# Osmofl2k_adapter_threechannel.net
KiCad netlist of a schematic drawn in EAGLE
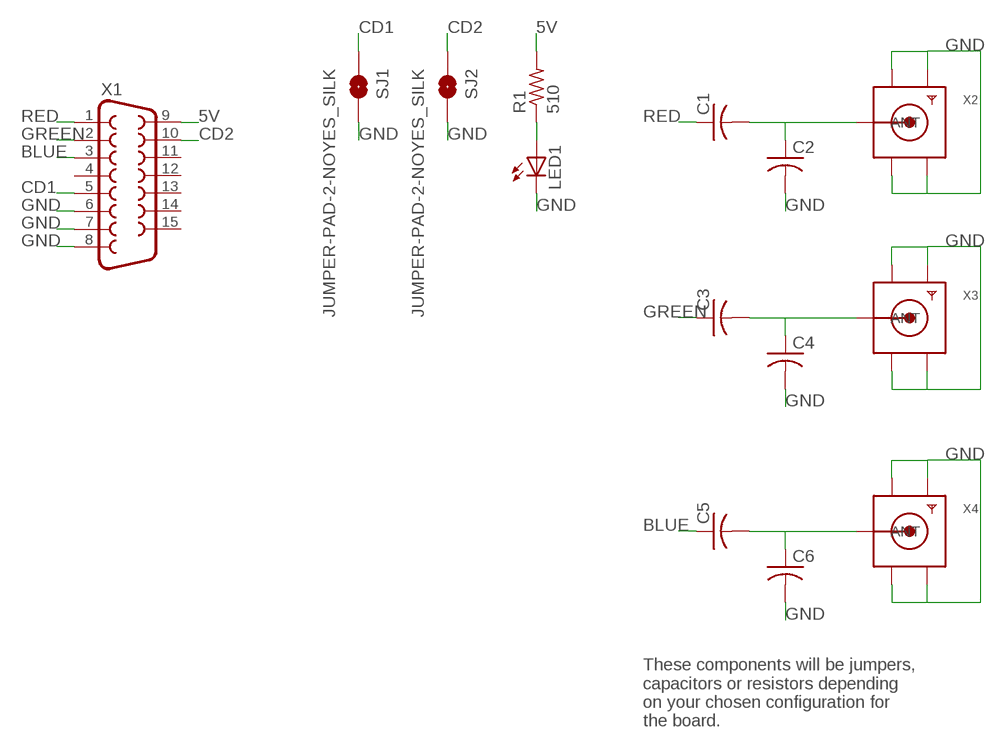
[diagram p0: schematic, sheet 1]

(export (version "E")
  (design (tool "Eeschema 10.0.6"))
  (components
    (comp (ref "C1")
      (value "C-USC0603")
      (footprint "eagle-import:C0603")
      (libsource (lib "eagle-import") (part "C-USC0603"))
    )
    (comp (ref "C2")
      (value "C-USC0603")
      (footprint "eagle-import:C0603")
      (libsource (lib "eagle-import") (part "C-USC0603"))
    )
    (comp (ref "C3")
      (value "C-USC0603")
      (footprint "eagle-import:C0603")
      (libsource (lib "eagle-import") (part "C-USC0603"))
    )
    (comp (ref "C4")
      (value "C-USC0603")
      (footprint "eagle-import:C0603")
      (libsource (lib "eagle-import") (part "C-USC0603"))
    )
    (comp (ref "C5")
      (value "C-USC0603")
      (footprint "eagle-import:C0603")
      (libsource (lib "eagle-import") (part "C-USC0603"))
    )
    (comp (ref "C6")
      (value "C-USC0603")
      (footprint "eagle-import:C0603")
      (libsource (lib "eagle-import") (part "C-USC0603"))
    )
    (comp (ref "LED1")
      (value "LEDCHIPLED_0805")
      (footprint "eagle-import:CHIPLED_0805")
      (libsource (lib "eagle-import") (part "LEDCHIPLED_0805"))
    )
    (comp (ref "R1")
      (value "510")
      (footprint "eagle-import:R0805")
      (libsource (lib "eagle-import") (part "R-US_R0805"))
    )
    (comp (ref "SJ1")
      (value "JUMPER-PAD-2-NOYES_SILK")
      (footprint "eagle-import:PAD-JUMPER-2-NO_YES_SILK")
      (libsource (lib "eagle-import") (part "JUMPER-PAD-2-NOYES_SILK"))
    )
    (comp (ref "SJ2")
      (value "JUMPER-PAD-2-NOYES_SILK")
      (footprint "eagle-import:PAD-JUMPER-2-NO_YES_SILK")
      (libsource (lib "eagle-import") (part "JUMPER-PAD-2-NOYES_SILK"))
    )
    (comp (ref "X1")
      (value "F15HDH")
      (footprint "eagle-import:HDF15H")
      (libsource (lib "eagle-import") (part "F15HDH"))
    )
    (comp (ref "X2")
      (value "SMACONNECTOR_EDGE")
      (footprint "eagle-import:SMA_EDGELAUNCH")
      (libsource (lib "eagle-import") (part "SMACONNECTOR_EDGE"))
    )
    (comp (ref "X3")
      (value "SMACONNECTOR_EDGE")
      (footprint "eagle-import:SMA_EDGELAUNCH")
      (libsource (lib "eagle-import") (part "SMACONNECTOR_EDGE"))
    )
    (comp (ref "X4")
      (value "SMACONNECTOR_EDGE")
      (footprint "eagle-import:SMA_EDGELAUNCH")
      (libsource (lib "eagle-import") (part "SMACONNECTOR_EDGE"))
    )
  )
  (nets
    (net (code "1") (name "/5V") (class "Default")
      (node (ref "R1") (pin "2") (pinfunction "2_2") (pintype "passive"))
      (node (ref "X1") (pin "9") (pinfunction "9_9") (pintype "passive"))
    )
    (net (code "2") (name "/BLUE") (class "Default")
      (node (ref "C5") (pin "1") (pinfunction "1_1") (pintype "passive"))
      (node (ref "X1") (pin "3") (pinfunction "3_3") (pintype "passive"))
    )
    (net (code "3") (name "/CD1") (class "Default")
      (node (ref "SJ1") (pin "1") (pinfunction "1_1") (pintype "passive"))
      (node (ref "X1") (pin "5") (pinfunction "5_5") (pintype "passive"))
    )
    (net (code "4") (name "/CD2") (class "Default")
      (node (ref "SJ2") (pin "1") (pinfunction "1_1") (pintype "passive"))
      (node (ref "X1") (pin "10") (pinfunction "10_10") (pintype "passive"))
    )
    (net (code "5") (name "/GND") (class "Default")
      (node (ref "C2") (pin "2") (pinfunction "2_2") (pintype "passive"))
      (node (ref "C4") (pin "2") (pinfunction "2_2") (pintype "passive"))
      (node (ref "C6") (pin "2") (pinfunction "2_2") (pintype "passive"))
      (node (ref "LED1") (pin "C") (pinfunction "C_C") (pintype "passive"))
      (node (ref "SJ1") (pin "2") (pinfunction "2_2") (pintype "passive"))
      (node (ref "SJ2") (pin "2") (pinfunction "2_2") (pintype "passive"))
      (node (ref "X1") (pin "6") (pinfunction "6_6") (pintype "passive"))
      (node (ref "X1") (pin "7") (pinfunction "7_7") (pintype "passive"))
      (node (ref "X1") (pin "8") (pinfunction "8_8") (pintype "passive"))
      (node (ref "X2") (pin "GND@1") (pinfunction "GND4_GND@1") (pintype "power_in"))
      (node (ref "X2") (pin "GND@2") (pinfunction "GND3_GND@2") (pintype "power_in"))
      (node (ref "X2") (pin "GND@3") (pinfunction "GND2_GND@3") (pintype "power_in"))
      (node (ref "X2") (pin "GND@4") (pinfunction "GND1_GND@4") (pintype "power_in"))
      (node (ref "X3") (pin "GND@1") (pinfunction "GND4_GND@1") (pintype "power_in"))
      (node (ref "X3") (pin "GND@2") (pinfunction "GND3_GND@2") (pintype "power_in"))
      (node (ref "X3") (pin "GND@3") (pinfunction "GND2_GND@3") (pintype "power_in"))
      (node (ref "X3") (pin "GND@4") (pinfunction "GND1_GND@4") (pintype "power_in"))
      (node (ref "X4") (pin "GND@1") (pinfunction "GND4_GND@1") (pintype "power_in"))
      (node (ref "X4") (pin "GND@2") (pinfunction "GND3_GND@2") (pintype "power_in"))
      (node (ref "X4") (pin "GND@3") (pinfunction "GND2_GND@3") (pintype "power_in"))
      (node (ref "X4") (pin "GND@4") (pinfunction "GND1_GND@4") (pintype "power_in"))
    )
    (net (code "6") (name "/GREEN") (class "Default")
      (node (ref "C3") (pin "1") (pinfunction "1_1") (pintype "passive"))
      (node (ref "X1") (pin "2") (pinfunction "2_2") (pintype "passive"))
    )
    (net (code "7") (name "/RED") (class "Default")
      (node (ref "C1") (pin "1") (pinfunction "1_1") (pintype "passive"))
      (node (ref "X1") (pin "1") (pinfunction "1_1") (pintype "passive"))
    )
    (net (code "8") (name "Net-(LED1-PadA)") (class "Default")
      (node (ref "LED1") (pin "A") (pinfunction "A_A") (pintype "passive"))
      (node (ref "R1") (pin "1") (pinfunction "1_1") (pintype "passive"))
    )
    (net (code "9") (name "Net-(X2-ANT)") (class "Default")
      (node (ref "C1") (pin "2") (pinfunction "2_2") (pintype "passive"))
      (node (ref "C2") (pin "1") (pinfunction "1_1") (pintype "passive"))
      (node (ref "X2") (pin "P") (pinfunction "ANT_P") (pintype "bidirectional"))
    )
    (net (code "10") (name "Net-(X3-ANT)") (class "Default")
      (node (ref "C3") (pin "2") (pinfunction "2_2") (pintype "passive"))
      (node (ref "C4") (pin "1") (pinfunction "1_1") (pintype "passive"))
      (node (ref "X3") (pin "P") (pinfunction "ANT_P") (pintype "bidirectional"))
    )
    (net (code "11") (name "Net-(X4-ANT)") (class "Default")
      (node (ref "C5") (pin "2") (pinfunction "2_2") (pintype "passive"))
      (node (ref "C6") (pin "1") (pinfunction "1_1") (pintype "passive"))
      (node (ref "X4") (pin "P") (pinfunction "ANT_P") (pintype "bidirectional"))
    )
    (net (code "12") (name "unconnected-(X1-Pad4)") (class "Default")
      (node (ref "X1") (pin "4") (pinfunction "4_4") (pintype "passive"))
    )
    (net (code "13") (name "unconnected-(X1-Pad11)") (class "Default")
      (node (ref "X1") (pin "11") (pinfunction "11_11") (pintype "passive"))
    )
    (net (code "14") (name "unconnected-(X1-Pad12)") (class "Default")
      (node (ref "X1") (pin "12") (pinfunction "12_12") (pintype "passive"))
    )
    (net (code "15") (name "unconnected-(X1-Pad13)") (class "Default")
      (node (ref "X1") (pin "13") (pinfunction "13_13") (pintype "passive"))
    )
    (net (code "16") (name "unconnected-(X1-Pad14)") (class "Default")
      (node (ref "X1") (pin "14") (pinfunction "14_14") (pintype "passive"))
    )
    (net (code "17") (name "unconnected-(X1-Pad15)") (class "Default")
      (node (ref "X1") (pin "15") (pinfunction "15_15") (pintype "passive"))
    )
  )
)
